# FT231X-USBserial.net
KiCad netlist of a schematic drawn in EAGLE
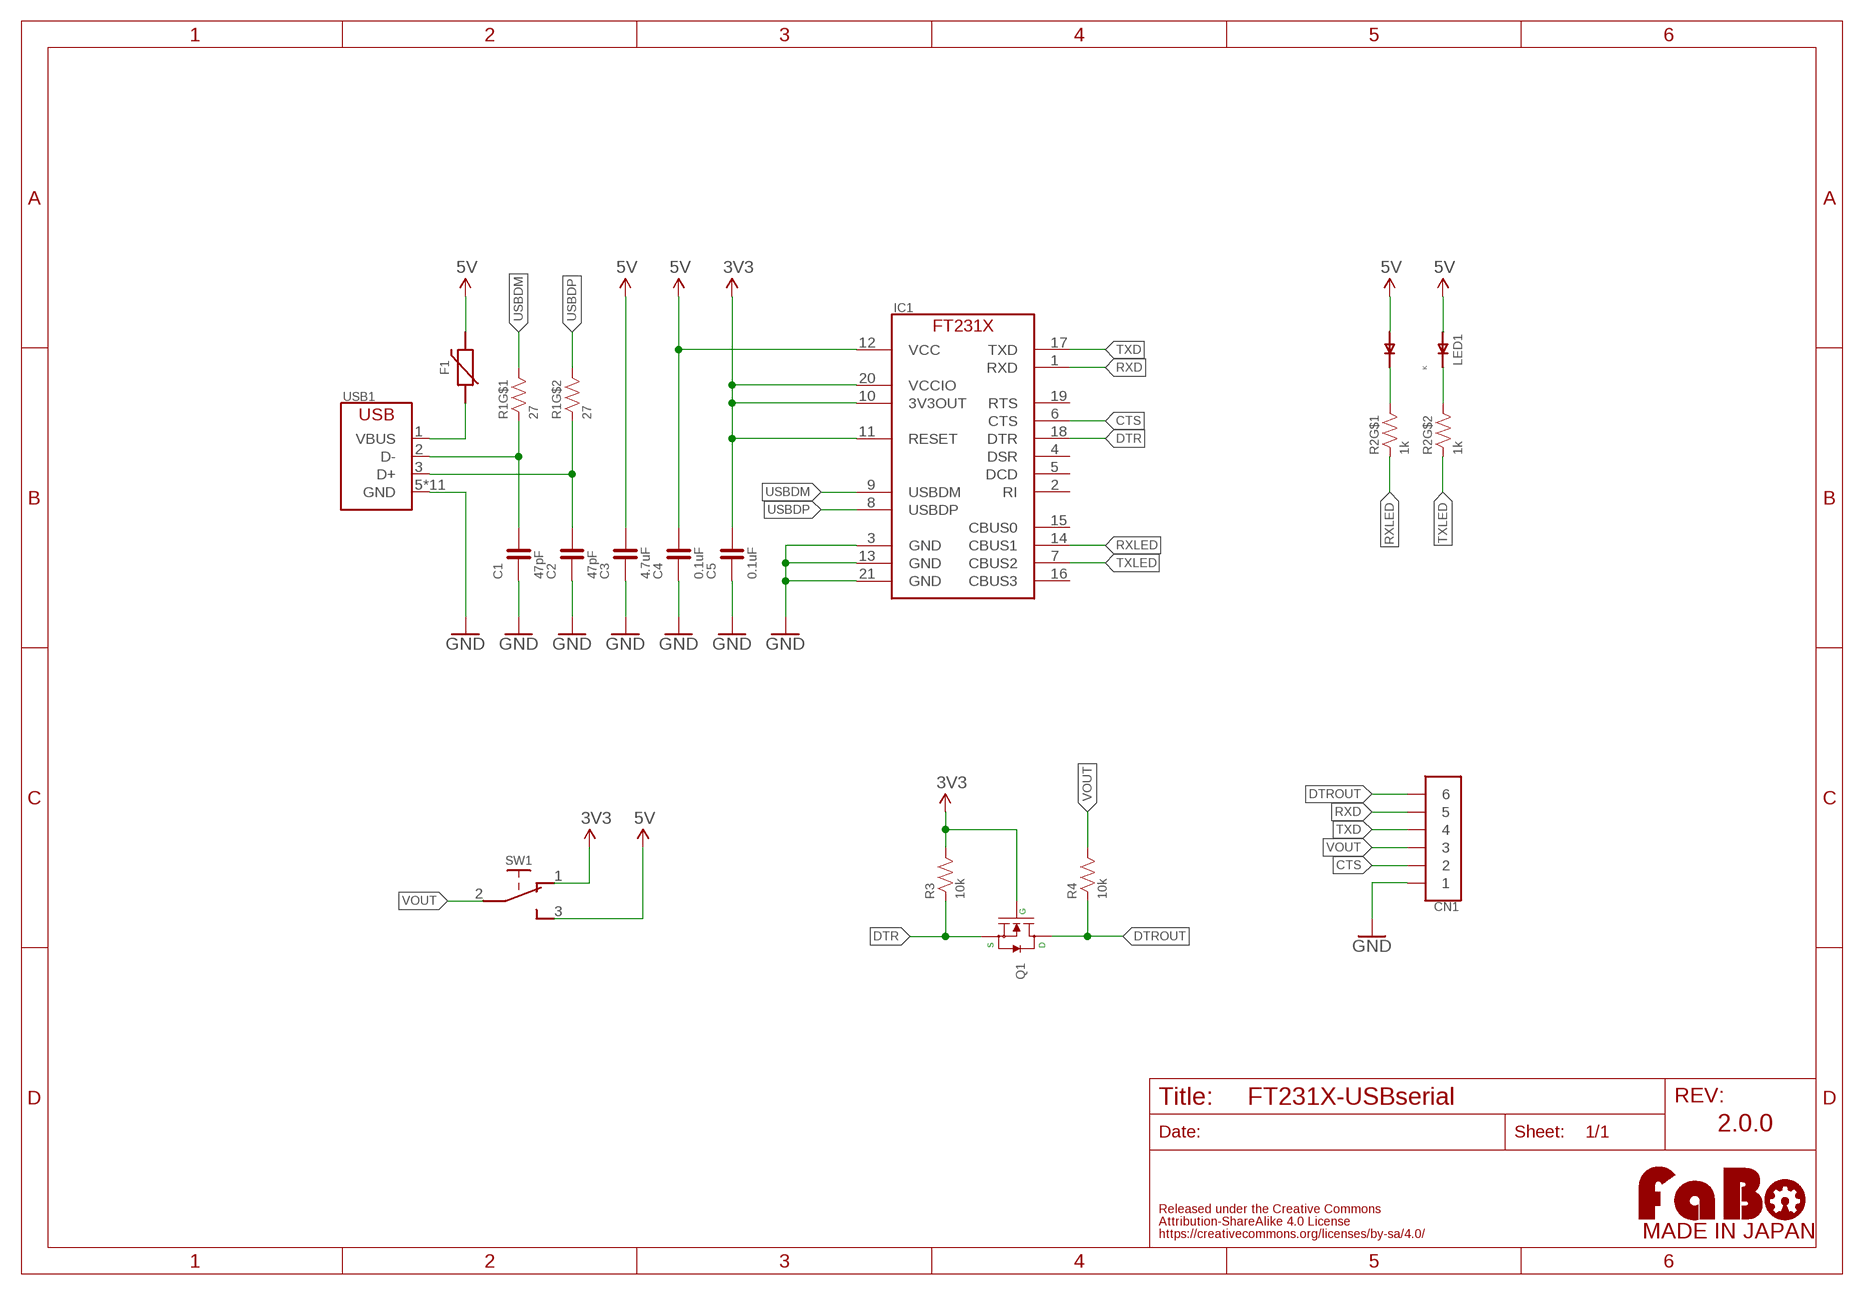
[diagram p0: schematic, sheet 1]

(export (version "E")
  (design (tool "Eeschema 10.0.6"))
  (components
    (comp (ref "C1")
      (value "47pF")
      (footprint "eagle-import:EIA0603")
      (libsource (lib "eagle-import") (part "CAPACITOR-0603"))
    )
    (comp (ref "C2")
      (value "47pF")
      (footprint "eagle-import:EIA0603")
      (libsource (lib "eagle-import") (part "CAPACITOR-0603"))
    )
    (comp (ref "C3")
      (value "4.7uF")
      (footprint "eagle-import:EIA0603")
      (libsource (lib "eagle-import") (part "CAPACITOR-0603"))
    )
    (comp (ref "C4")
      (value "0.1uF")
      (footprint "eagle-import:EIA0603")
      (libsource (lib "eagle-import") (part "CAPACITOR-0603"))
    )
    (comp (ref "C5")
      (value "0.1uF")
      (footprint "eagle-import:EIA0603")
      (libsource (lib "eagle-import") (part "CAPACITOR-0603"))
    )
    (comp (ref "CN1")
      (value "PIN_1X6_NARROW")
      (footprint "eagle-import:PIN_1X6_NARROW")
      (libsource (lib "eagle-import") (part "PIN_1X6_NARROW"))
    )
    (comp (ref "F1")
      (value "PPTC-NANO")
      (footprint "eagle-import:NANOSMDC035F")
      (libsource (lib "eagle-import") (part "PPTC-NANO"))
    )
    (comp (ref "IC1")
      (value "FT231XQ")
      (footprint "eagle-import:QFN-20")
      (libsource (lib "eagle-import") (part "FT231XQ"))
    )
    (comp (ref "LED1")
      (value "HSMF-C16X")
      (footprint "eagle-import:HSMF-C16X")
      (libsource (lib "eagle-import") (part "HSMF-C16X"))
    )
    (comp (ref "LOGO1")
      (value "LOGO_FABO-M_BOTTOM")
      (footprint "eagle-import:LOGO_FABO_M_BOTTOM")
      (libsource (lib "eagle-import") (part "LOGO_FABO-M_BOTTOM"))
    )
    (comp (ref "Q1")
      (value "MOSFET-N")
      (footprint "eagle-import:SOT-23-3")
      (libsource (lib "eagle-import") (part "MOSFET-N"))
    )
    (comp (ref "R1")
      (value "27")
      (footprint "eagle-import:EXBV4V")
      (libsource (lib "eagle-import") (part "RESISTOR_ARRAY_2"))
    )
    (comp (ref "R2")
      (value "1k")
      (footprint "eagle-import:EXBV4V")
      (libsource (lib "eagle-import") (part "RESISTOR_ARRAY_2"))
    )
    (comp (ref "R3")
      (value "10k")
      (footprint "eagle-import:EIA0603")
      (libsource (lib "eagle-import") (part "RESISTOR-0603"))
    )
    (comp (ref "R4")
      (value "10k")
      (footprint "eagle-import:EIA0603")
      (libsource (lib "eagle-import") (part "RESISTOR-0603"))
    )
    (comp (ref "SW1")
      (value "SWITCH-SLIDE")
      (footprint "eagle-import:SSSS810701")
      (libsource (lib "eagle-import") (part "SWITCH-SLIDE"))
    )
    (comp (ref "USB1")
      (value "USB-ZX62D")
      (footprint "eagle-import:ZX62D-B-5PA8")
      (libsource (lib "eagle-import") (part "USB-ZX62D"))
    )
  )
  (nets
    (net (code "1") (name "3V3") (class "Default")
      (node (ref "C5") (pin "2") (pinfunction "2_2") (pintype "passive"))
      (node (ref "IC1") (pin "10") (pinfunction "3V3OUT_10") (pintype "bidirectional"))
      (node (ref "IC1") (pin "11") (pinfunction "RESET_11") (pintype "bidirectional"))
      (node (ref "IC1") (pin "20") (pinfunction "VCCIO_20") (pintype "bidirectional"))
      (node (ref "Q1") (pin "1") (pinfunction "G_1") (pintype "passive"))
      (node (ref "R3") (pin "2") (pinfunction "2_2") (pintype "bidirectional"))
      (node (ref "SW1") (pin "1") (pinfunction "1_1") (pintype "passive"))
    )
    (net (code "2") (name "5V") (class "Default")
      (node (ref "C3") (pin "2") (pinfunction "2_2") (pintype "passive"))
      (node (ref "C4") (pin "2") (pinfunction "2_2") (pintype "passive"))
      (node (ref "F1") (pin "2") (pinfunction "2_2") (pintype "bidirectional"))
      (node (ref "IC1") (pin "12") (pinfunction "VCC_12") (pintype "bidirectional"))
      (node (ref "LED1") (pin "1") (pinfunction "A1_1") (pintype "passive"))
      (node (ref "LED1") (pin "2") (pinfunction "A2_2") (pintype "bidirectional"))
      (node (ref "SW1") (pin "3") (pinfunction "3_3") (pintype "passive"))
    )
    (net (code "3") (name "CTS") (class "Default")
      (node (ref "CN1") (pin "2") (pinfunction "2_2") (pintype "bidirectional"))
      (node (ref "IC1") (pin "6") (pinfunction "CTS_6") (pintype "bidirectional"))
    )
    (net (code "4") (name "DTR") (class "Default")
      (node (ref "IC1") (pin "18") (pinfunction "DTR_18") (pintype "bidirectional"))
      (node (ref "Q1") (pin "2") (pinfunction "S_2") (pintype "passive"))
      (node (ref "R3") (pin "1") (pinfunction "1_1") (pintype "bidirectional"))
    )
    (net (code "5") (name "DTROUT") (class "Default")
      (node (ref "CN1") (pin "6") (pinfunction "6_6") (pintype "bidirectional"))
      (node (ref "Q1") (pin "3") (pinfunction "D_3") (pintype "passive"))
      (node (ref "R4") (pin "1") (pinfunction "1_1") (pintype "bidirectional"))
    )
    (net (code "6") (name "GND") (class "Default")
      (node (ref "C1") (pin "1") (pinfunction "1_1") (pintype "passive"))
      (node (ref "C2") (pin "1") (pinfunction "1_1") (pintype "passive"))
      (node (ref "C3") (pin "1") (pinfunction "1_1") (pintype "passive"))
      (node (ref "C4") (pin "1") (pinfunction "1_1") (pintype "passive"))
      (node (ref "C5") (pin "1") (pinfunction "1_1") (pintype "passive"))
      (node (ref "CN1") (pin "1") (pinfunction "1_1") (pintype "bidirectional"))
      (node (ref "IC1") (pin "13") (pinfunction "GND_13") (pintype "bidirectional"))
      (node (ref "IC1") (pin "21") (pinfunction "GND_21") (pintype "bidirectional"))
      (node (ref "IC1") (pin "3") (pinfunction "GND_3") (pintype "bidirectional"))
      (node (ref "USB1") (pin "5") (pinfunction "GND_5") (pintype "bidirectional"))
      (node (ref "USB1") (pin "B1") (pinfunction "GND_B1") (pintype "bidirectional"))
      (node (ref "USB1") (pin "B2") (pinfunction "GND_B2") (pintype "bidirectional"))
      (node (ref "USB1") (pin "B3") (pinfunction "GND_B3") (pintype "bidirectional"))
      (node (ref "USB1") (pin "B4") (pinfunction "GND_B4") (pintype "bidirectional"))
      (node (ref "USB1") (pin "T1") (pinfunction "GND_T1") (pintype "bidirectional"))
      (node (ref "USB1") (pin "T2") (pinfunction "GND_T2") (pintype "bidirectional"))
      (node (ref "USB1") (pin "T3") (pinfunction "GND_T3") (pintype "bidirectional"))
      (node (ref "USB1") (pin "T4") (pinfunction "GND_T4") (pintype "bidirectional"))
      (node (ref "USB1") (pin "T5") (pinfunction "GND_T5") (pintype "bidirectional"))
      (node (ref "USB1") (pin "T6") (pinfunction "GND_T6") (pintype "bidirectional"))
    )
    (net (code "7") (name "Net-(LED1-K1)") (class "Default")
      (node (ref "LED1") (pin "3") (pinfunction "K1_3") (pintype "passive"))
      (node (ref "R2") (pin "3") (pinfunction "2_3") (pintype "bidirectional"))
    )
    (net (code "8") (name "Net-(LED1-K2)") (class "Default")
      (node (ref "LED1") (pin "4") (pinfunction "K2_4") (pintype "bidirectional"))
      (node (ref "R2") (pin "4") (pinfunction "2_4") (pintype "bidirectional"))
    )
    (net (code "9") (name "Net-(R1B-1)") (class "Default")
      (node (ref "C2") (pin "2") (pinfunction "2_2") (pintype "passive"))
      (node (ref "R1") (pin "2") (pinfunction "1_2") (pintype "bidirectional"))
      (node (ref "USB1") (pin "3") (pinfunction "D+_3") (pintype "bidirectional"))
    )
    (net (code "10") (name "Net-(USB1-D-)") (class "Default")
      (node (ref "C1") (pin "2") (pinfunction "2_2") (pintype "passive"))
      (node (ref "R1") (pin "1") (pinfunction "1_1") (pintype "bidirectional"))
      (node (ref "USB1") (pin "2") (pinfunction "D-_2") (pintype "bidirectional"))
    )
    (net (code "11") (name "Net-(USB1-VBUS)") (class "Default")
      (node (ref "F1") (pin "1") (pinfunction "1_1") (pintype "bidirectional"))
      (node (ref "USB1") (pin "1") (pinfunction "VBUS_1") (pintype "bidirectional"))
    )
    (net (code "12") (name "RXD") (class "Default")
      (node (ref "CN1") (pin "5") (pinfunction "5_5") (pintype "bidirectional"))
      (node (ref "IC1") (pin "1") (pinfunction "RXD_1") (pintype "bidirectional"))
    )
    (net (code "13") (name "RXLED") (class "Default")
      (node (ref "IC1") (pin "14") (pinfunction "CBUS1_14") (pintype "bidirectional"))
      (node (ref "R2") (pin "1") (pinfunction "1_1") (pintype "bidirectional"))
    )
    (net (code "14") (name "TXD") (class "Default")
      (node (ref "CN1") (pin "4") (pinfunction "4_4") (pintype "bidirectional"))
      (node (ref "IC1") (pin "17") (pinfunction "TXD_17") (pintype "bidirectional"))
    )
    (net (code "15") (name "TXLED") (class "Default")
      (node (ref "IC1") (pin "7") (pinfunction "CBUS2_7") (pintype "bidirectional"))
      (node (ref "R2") (pin "2") (pinfunction "1_2") (pintype "bidirectional"))
    )
    (net (code "16") (name "USBDM") (class "Default")
      (node (ref "IC1") (pin "9") (pinfunction "USBDM_9") (pintype "bidirectional"))
      (node (ref "R1") (pin "4") (pinfunction "2_4") (pintype "bidirectional"))
    )
    (net (code "17") (name "USBDP") (class "Default")
      (node (ref "IC1") (pin "8") (pinfunction "USBDP_8") (pintype "bidirectional"))
      (node (ref "R1") (pin "3") (pinfunction "2_3") (pintype "bidirectional"))
    )
    (net (code "18") (name "VOUT") (class "Default")
      (node (ref "CN1") (pin "3") (pinfunction "3_3") (pintype "bidirectional"))
      (node (ref "R4") (pin "2") (pinfunction "2_2") (pintype "bidirectional"))
      (node (ref "SW1") (pin "2") (pinfunction "2_2") (pintype "passive"))
    )
    (net (code "19") (name "unconnected-(IC1-CBUS0-Pad15)") (class "Default")
      (node (ref "IC1") (pin "15") (pinfunction "CBUS0_15") (pintype "bidirectional"))
    )
    (net (code "20") (name "unconnected-(IC1-CBUS3-Pad16)") (class "Default")
      (node (ref "IC1") (pin "16") (pinfunction "CBUS3_16") (pintype "bidirectional"))
    )
    (net (code "21") (name "unconnected-(IC1-DCD-Pad5)") (class "Default")
      (node (ref "IC1") (pin "5") (pinfunction "DCD_5") (pintype "bidirectional"))
    )
    (net (code "22") (name "unconnected-(IC1-DSR-Pad4)") (class "Default")
      (node (ref "IC1") (pin "4") (pinfunction "DSR_4") (pintype "bidirectional"))
    )
    (net (code "23") (name "unconnected-(IC1-RI-Pad2)") (class "Default")
      (node (ref "IC1") (pin "2") (pinfunction "RI_2") (pintype "bidirectional"))
    )
    (net (code "24") (name "unconnected-(IC1-RTS-Pad19)") (class "Default")
      (node (ref "IC1") (pin "19") (pinfunction "RTS_19") (pintype "bidirectional"))
    )
  )
)
